# arduino_shield_schematic.net
KiCad netlist of a schematic drawn in EAGLE
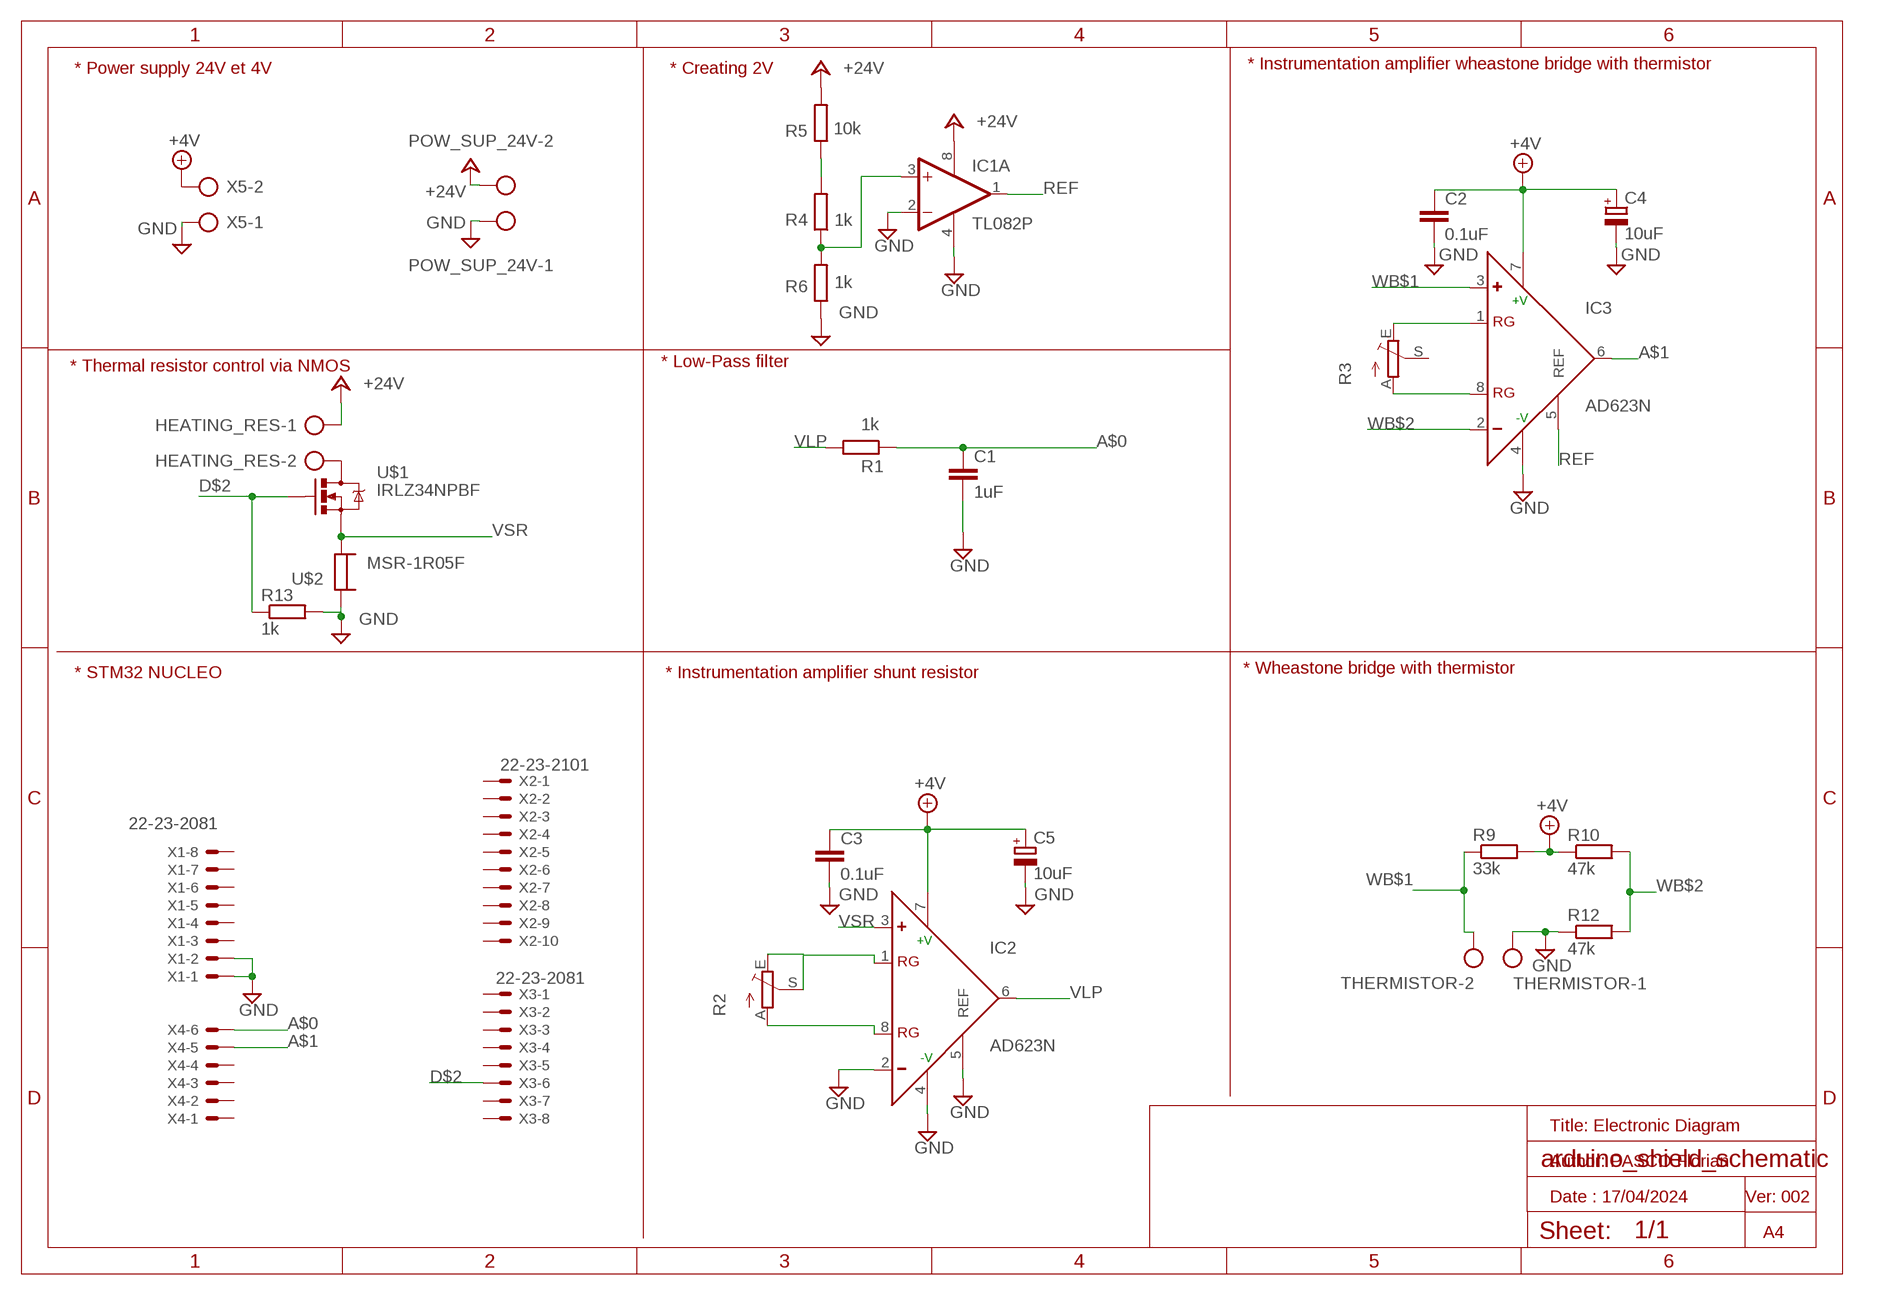
[diagram p0: schematic, sheet 1]

(export (version "E")
  (design (tool "Eeschema 10.0.6"))
  (components
    (comp (ref "C1")
      (value "1uF")
      (footprint "eagle-import:C025-025X050")
      (libsource (lib "eagle-import") (part "C-EU025-025X050"))
    )
    (comp (ref "C2")
      (value "0.1uF")
      (footprint "eagle-import:C025-025X050")
      (libsource (lib "eagle-import") (part "C-EU025-025X050"))
    )
    (comp (ref "C3")
      (value "0.1uF")
      (footprint "eagle-import:C025-025X050")
      (libsource (lib "eagle-import") (part "C-EU025-025X050"))
    )
    (comp (ref "C4")
      (value "10uF")
      (footprint "eagle-import:E2,5-6E")
      (libsource (lib "eagle-import") (part "CPOL-EUE2,5-6E"))
    )
    (comp (ref "C5")
      (value "10uF")
      (footprint "eagle-import:E2,5-6E")
      (libsource (lib "eagle-import") (part "CPOL-EUE2,5-6E"))
    )
    (comp (ref "HEATING_RES")
      (value "AK300/2")
      (footprint "eagle-import:AK300_2")
      (libsource (lib "eagle-import") (part "AK300/2"))
    )
    (comp (ref "IC1")
      (value "TL082P")
      (footprint "eagle-import:DIL08")
      (libsource (lib "eagle-import") (part "TL082P"))
    )
    (comp (ref "IC2")
      (value "AD623N")
      (footprint "eagle-import:DIL08")
      (fields (field (name "MF") "ALTERA CORPORATION") (field (name "MPN") "AD623ANZ"))
      (libsource (lib "eagle-import") (part "AD623N"))
    )
    (comp (ref "IC3")
      (value "AD623N")
      (footprint "eagle-import:DIL08")
      (fields (field (name "MF") "ALTERA CORPORATION") (field (name "MPN") "AD623ANZ"))
      (libsource (lib "eagle-import") (part "AD623N"))
    )
    (comp (ref "POW_SUP_24V")
      (value "AK300/2")
      (footprint "eagle-import:AK300_2")
      (libsource (lib "eagle-import") (part "AK300/2"))
    )
    (comp (ref "R1")
      (value "1k")
      (footprint "eagle-import:0207_10")
      (libsource (lib "eagle-import") (part "R-EU_0207/10"))
    )
    (comp (ref "R2")
      (value "TRIM_EU-S64W")
      (footprint "eagle-import:S64W")
      (libsource (lib "eagle-import") (part "TRIM_EU-S64W"))
    )
    (comp (ref "R3")
      (value "TRIM_EU-S64W")
      (footprint "eagle-import:S64W")
      (libsource (lib "eagle-import") (part "TRIM_EU-S64W"))
    )
    (comp (ref "R4")
      (value "1k")
      (footprint "eagle-import:0207_10")
      (libsource (lib "eagle-import") (part "R-EU_0207/10"))
    )
    (comp (ref "R5")
      (value "10k")
      (footprint "eagle-import:0207_10")
      (libsource (lib "eagle-import") (part "R-EU_0207/10"))
    )
    (comp (ref "R6")
      (value "1k")
      (footprint "eagle-import:0207_10")
      (libsource (lib "eagle-import") (part "R-EU_0207/10"))
    )
    (comp (ref "R9")
      (value "33k")
      (footprint "eagle-import:0207_10")
      (libsource (lib "eagle-import") (part "R-EU_0207/10"))
    )
    (comp (ref "R10")
      (value "47k")
      (footprint "eagle-import:0207_10")
      (libsource (lib "eagle-import") (part "R-EU_0207/10"))
    )
    (comp (ref "R12")
      (value "47k")
      (footprint "eagle-import:0207_10")
      (libsource (lib "eagle-import") (part "R-EU_0207/10"))
    )
    (comp (ref "R13")
      (value "1k")
      (footprint "eagle-import:0207_10")
      (libsource (lib "eagle-import") (part "R-EU_0207/10"))
    )
    (comp (ref "THERMISTOR")
      (value "AK300/2")
      (footprint "eagle-import:AK300_2")
      (libsource (lib "eagle-import") (part "AK300/2"))
    )
    (comp (ref "U$1")
      (value "IRLZ34NPBF")
      (footprint "eagle-import:TO-220(2)")
      (fields (field (name "MF") "Infineon"))
      (libsource (lib "eagle-import") (part "IRLZ34NPBF"))
    )
    (comp (ref "U$2")
      (value "MSR-1R05F")
      (footprint "eagle-import:MSR1")
      (libsource (lib "eagle-import") (part "MSR-1R05F"))
    )
    (comp (ref "X1")
      (value "22-23-2081")
      (footprint "eagle-import:22-23-2081")
      (fields (field (name "MF") "MOLEX"))
      (libsource (lib "eagle-import") (part "22-23-2081"))
    )
    (comp (ref "X2")
      (value "22-23-2101")
      (footprint "eagle-import:22-23-2101")
      (fields (field (name "MF") "MOLEX"))
      (libsource (lib "eagle-import") (part "22-23-2101"))
    )
    (comp (ref "X3")
      (value "22-23-2081")
      (footprint "eagle-import:22-23-2081")
      (fields (field (name "MF") "MOLEX"))
      (libsource (lib "eagle-import") (part "22-23-2081"))
    )
    (comp (ref "X4")
      (value "22-23-2061")
      (footprint "eagle-import:22-23-2061")
      (fields (field (name "MF") "MOLEX"))
      (libsource (lib "eagle-import") (part "22-23-2061"))
    )
    (comp (ref "X5")
      (value "AK300/2")
      (footprint "eagle-import:AK300_2")
      (libsource (lib "eagle-import") (part "AK300/2"))
    )
  )
  (nets
    (net (code "1") (name "+4V") (class "Default")
      (node (ref "C2") (pin "1") (pinfunction "1_1") (pintype "passive"))
      (node (ref "C3") (pin "1") (pinfunction "1_1") (pintype "passive"))
      (node (ref "C4") (pin "+") (pinfunction "+_+") (pintype "passive"))
      (node (ref "C5") (pin "+") (pinfunction "+_+") (pintype "passive"))
      (node (ref "IC2") (pin "7") (pinfunction "+V_7") (pintype "power_in"))
      (node (ref "IC3") (pin "7") (pinfunction "+V_7") (pintype "power_in"))
      (node (ref "R10") (pin "1") (pinfunction "1_1") (pintype "passive"))
      (node (ref "R9") (pin "2") (pinfunction "2_2") (pintype "passive"))
      (node (ref "X5") (pin "2") (pinfunction "KL_2") (pintype "passive"))
    )
    (net (code "2") (name "+24V") (class "Default")
      (node (ref "HEATING_RES") (pin "1") (pinfunction "KL_1") (pintype "passive"))
      (node (ref "IC1") (pin "8") (pinfunction "V+_8") (pintype "power_in"))
      (node (ref "POW_SUP_24V") (pin "2") (pinfunction "KL_2") (pintype "passive"))
      (node (ref "R5") (pin "2") (pinfunction "2_2") (pintype "passive"))
    )
    (net (code "3") (name "/A$0") (class "Default")
      (node (ref "C1") (pin "1") (pinfunction "1_1") (pintype "passive"))
      (node (ref "R1") (pin "1") (pinfunction "1_1") (pintype "passive"))
      (node (ref "X4") (pin "6") (pinfunction "S_6") (pintype "passive"))
    )
    (net (code "4") (name "/A$1") (class "Default")
      (node (ref "IC3") (pin "6") (pinfunction "OUT_6") (pintype "output"))
      (node (ref "X4") (pin "5") (pinfunction "S_5") (pintype "passive"))
    )
    (net (code "5") (name "/D$2") (class "Default")
      (node (ref "R13") (pin "1") (pinfunction "1_1") (pintype "passive"))
      (node (ref "U$1") (pin "IN") (pinfunction "G_IN") (pintype "passive"))
      (node (ref "X3") (pin "6") (pinfunction "S_6") (pintype "passive"))
    )
    (net (code "6") (name "/REF") (class "Default")
      (node (ref "IC1") (pin "1") (pinfunction "OUT_1") (pintype "output"))
      (node (ref "IC3") (pin "5") (pinfunction "REF_5") (pintype "passive"))
    )
    (net (code "7") (name "/VLP") (class "Default")
      (node (ref "IC2") (pin "6") (pinfunction "OUT_6") (pintype "output"))
      (node (ref "R1") (pin "2") (pinfunction "2_2") (pintype "passive"))
    )
    (net (code "8") (name "/VSR") (class "Default")
      (node (ref "IC2") (pin "3") (pinfunction "+_3") (pintype "input"))
      (node (ref "U$1") (pin "OUT") (pinfunction "S_OUT") (pintype "passive"))
      (node (ref "U$2") (pin "P$1") (pinfunction "1_P$1") (pintype "passive"))
    )
    (net (code "9") (name "/WB$1") (class "Default")
      (node (ref "IC3") (pin "3") (pinfunction "+_3") (pintype "input"))
      (node (ref "R9") (pin "1") (pinfunction "1_1") (pintype "passive"))
      (node (ref "THERMISTOR") (pin "2") (pinfunction "KL_2") (pintype "passive"))
    )
    (net (code "10") (name "/WB$2") (class "Default")
      (node (ref "IC3") (pin "2") (pinfunction "-_2") (pintype "input"))
      (node (ref "R10") (pin "2") (pinfunction "2_2") (pintype "passive"))
      (node (ref "R12") (pin "2") (pinfunction "2_2") (pintype "passive"))
    )
    (net (code "11") (name "GND") (class "Default")
      (node (ref "C1") (pin "2") (pinfunction "2_2") (pintype "passive"))
      (node (ref "C2") (pin "2") (pinfunction "2_2") (pintype "passive"))
      (node (ref "C3") (pin "2") (pinfunction "2_2") (pintype "passive"))
      (node (ref "C4") (pin "-") (pinfunction "-_-") (pintype "passive"))
      (node (ref "C5") (pin "-") (pinfunction "-_-") (pintype "passive"))
      (node (ref "IC1") (pin "2") (pinfunction "-IN_2") (pintype "input"))
      (node (ref "IC1") (pin "4") (pinfunction "V-_4") (pintype "power_in"))
      (node (ref "IC2") (pin "2") (pinfunction "-_2") (pintype "input"))
      (node (ref "IC2") (pin "4") (pinfunction "-V_4") (pintype "power_in"))
      (node (ref "IC2") (pin "5") (pinfunction "REF_5") (pintype "passive"))
      (node (ref "IC3") (pin "4") (pinfunction "-V_4") (pintype "power_in"))
      (node (ref "POW_SUP_24V") (pin "1") (pinfunction "KL_1") (pintype "passive"))
      (node (ref "R12") (pin "1") (pinfunction "1_1") (pintype "passive"))
      (node (ref "R13") (pin "2") (pinfunction "2_2") (pintype "passive"))
      (node (ref "R6") (pin "1") (pinfunction "1_1") (pintype "passive"))
      (node (ref "THERMISTOR") (pin "1") (pinfunction "KL_1") (pintype "passive"))
      (node (ref "U$2") (pin "P$2") (pinfunction "2_P$2") (pintype "passive"))
      (node (ref "X1") (pin "1") (pinfunction "S_1") (pintype "passive"))
      (node (ref "X1") (pin "2") (pinfunction "S_2") (pintype "passive"))
      (node (ref "X5") (pin "1") (pinfunction "KL_1") (pintype "passive"))
    )
    (net (code "12") (name "Net-(HEATING_RESB-KL)") (class "Default")
      (node (ref "HEATING_RES") (pin "2") (pinfunction "KL_2") (pintype "passive"))
      (node (ref "U$1") (pin "GND") (pinfunction "D_GND") (pintype "passive"))
    )
    (net (code "13") (name "Net-(IC1A-+IN)") (class "Default")
      (node (ref "IC1") (pin "3") (pinfunction "+IN_3") (pintype "input"))
      (node (ref "R4") (pin "1") (pinfunction "1_1") (pintype "passive"))
      (node (ref "R6") (pin "2") (pinfunction "2_2") (pintype "passive"))
    )
    (net (code "14") (name "Net-(IC2-RG-Pad8)") (class "Default")
      (node (ref "IC2") (pin "8") (pinfunction "RG_8") (pintype "passive"))
      (node (ref "R2") (pin "A") (pinfunction "A_A") (pintype "passive"))
    )
    (net (code "15") (name "Net-(IC3-RG-Pad1)") (class "Default")
      (node (ref "IC3") (pin "1") (pinfunction "RG_1") (pintype "passive"))
      (node (ref "R3") (pin "E") (pinfunction "E_E") (pintype "passive"))
    )
    (net (code "16") (name "Net-(IC3-RG-Pad8)") (class "Default")
      (node (ref "IC3") (pin "8") (pinfunction "RG_8") (pintype "passive"))
      (node (ref "R3") (pin "A") (pinfunction "A_A") (pintype "passive"))
    )
    (net (code "17") (name "Net-(R2-PadE)") (class "Default")
      (node (ref "R2") (pin "E") (pinfunction "E_E") (pintype "passive"))
      (node (ref "R2") (pin "S") (pinfunction "S_S") (pintype "passive"))
    )
    (net (code "18") (name "Net-(R4-Pad2)") (class "Default")
      (node (ref "R4") (pin "2") (pinfunction "2_2") (pintype "passive"))
      (node (ref "R5") (pin "1") (pinfunction "1_1") (pintype "passive"))
    )
    (net (code "19") (name "unconnected-(IC2-RG-Pad1)") (class "Default")
      (node (ref "IC2") (pin "1") (pinfunction "RG_1") (pintype "passive"))
    )
    (net (code "20") (name "unconnected-(R3-PadS)") (class "Default")
      (node (ref "R3") (pin "S") (pinfunction "S_S") (pintype "passive"))
    )
    (net (code "21") (name "unconnected-(X1C-S-Pad3)") (class "Default")
      (node (ref "X1") (pin "3") (pinfunction "S_3") (pintype "passive"))
    )
    (net (code "22") (name "unconnected-(X1D-S-Pad4)") (class "Default")
      (node (ref "X1") (pin "4") (pinfunction "S_4") (pintype "passive"))
    )
    (net (code "23") (name "unconnected-(X1E-S-Pad5)") (class "Default")
      (node (ref "X1") (pin "5") (pinfunction "S_5") (pintype "passive"))
    )
    (net (code "24") (name "unconnected-(X1F-S-Pad6)") (class "Default")
      (node (ref "X1") (pin "6") (pinfunction "S_6") (pintype "passive"))
    )
    (net (code "25") (name "unconnected-(X1G-S-Pad7)") (class "Default")
      (node (ref "X1") (pin "7") (pinfunction "S_7") (pintype "passive"))
    )
    (net (code "26") (name "unconnected-(X1H-S-Pad8)") (class "Default")
      (node (ref "X1") (pin "8") (pinfunction "S_8") (pintype "passive"))
    )
    (net (code "27") (name "unconnected-(X2A-S-Pad1)") (class "Default")
      (node (ref "X2") (pin "1") (pinfunction "S_1") (pintype "passive"))
    )
    (net (code "28") (name "unconnected-(X2B-S-Pad10)") (class "Default")
      (node (ref "X2") (pin "10") (pinfunction "S_10") (pintype "passive"))
    )
    (net (code "29") (name "unconnected-(X2C-S-Pad2)") (class "Default")
      (node (ref "X2") (pin "2") (pinfunction "S_2") (pintype "passive"))
    )
    (net (code "30") (name "unconnected-(X2D-S-Pad3)") (class "Default")
      (node (ref "X2") (pin "3") (pinfunction "S_3") (pintype "passive"))
    )
    (net (code "31") (name "unconnected-(X2E-S-Pad4)") (class "Default")
      (node (ref "X2") (pin "4") (pinfunction "S_4") (pintype "passive"))
    )
    (net (code "32") (name "unconnected-(X2F-S-Pad5)") (class "Default")
      (node (ref "X2") (pin "5") (pinfunction "S_5") (pintype "passive"))
    )
    (net (code "33") (name "unconnected-(X2G-S-Pad6)") (class "Default")
      (node (ref "X2") (pin "6") (pinfunction "S_6") (pintype "passive"))
    )
    (net (code "34") (name "unconnected-(X2H-S-Pad7)") (class "Default")
      (node (ref "X2") (pin "7") (pinfunction "S_7") (pintype "passive"))
    )
    (net (code "35") (name "unconnected-(X2I-S-Pad8)") (class "Default")
      (node (ref "X2") (pin "8") (pinfunction "S_8") (pintype "passive"))
    )
    (net (code "36") (name "unconnected-(X2J-S-Pad9)") (class "Default")
      (node (ref "X2") (pin "9") (pinfunction "S_9") (pintype "passive"))
    )
    (net (code "37") (name "unconnected-(X3A-S-Pad1)") (class "Default")
      (node (ref "X3") (pin "1") (pinfunction "S_1") (pintype "passive"))
    )
    (net (code "38") (name "unconnected-(X3B-S-Pad2)") (class "Default")
      (node (ref "X3") (pin "2") (pinfunction "S_2") (pintype "passive"))
    )
    (net (code "39") (name "unconnected-(X3C-S-Pad3)") (class "Default")
      (node (ref "X3") (pin "3") (pinfunction "S_3") (pintype "passive"))
    )
    (net (code "40") (name "unconnected-(X3D-S-Pad4)") (class "Default")
      (node (ref "X3") (pin "4") (pinfunction "S_4") (pintype "passive"))
    )
    (net (code "41") (name "unconnected-(X3E-S-Pad5)") (class "Default")
      (node (ref "X3") (pin "5") (pinfunction "S_5") (pintype "passive"))
    )
    (net (code "42") (name "unconnected-(X3G-S-Pad7)") (class "Default")
      (node (ref "X3") (pin "7") (pinfunction "S_7") (pintype "passive"))
    )
    (net (code "43") (name "unconnected-(X3H-S-Pad8)") (class "Default")
      (node (ref "X3") (pin "8") (pinfunction "S_8") (pintype "passive"))
    )
    (net (code "44") (name "unconnected-(X4A-S-Pad1)") (class "Default")
      (node (ref "X4") (pin "1") (pinfunction "S_1") (pintype "passive"))
    )
    (net (code "45") (name "unconnected-(X4B-S-Pad2)") (class "Default")
      (node (ref "X4") (pin "2") (pinfunction "S_2") (pintype "passive"))
    )
    (net (code "46") (name "unconnected-(X4C-S-Pad3)") (class "Default")
      (node (ref "X4") (pin "3") (pinfunction "S_3") (pintype "passive"))
    )
    (net (code "47") (name "unconnected-(X4D-S-Pad4)") (class "Default")
      (node (ref "X4") (pin "4") (pinfunction "S_4") (pintype "passive"))
    )
  )
)
